# powermgr.net
KiCad netlist of a schematic drawn in EAGLE
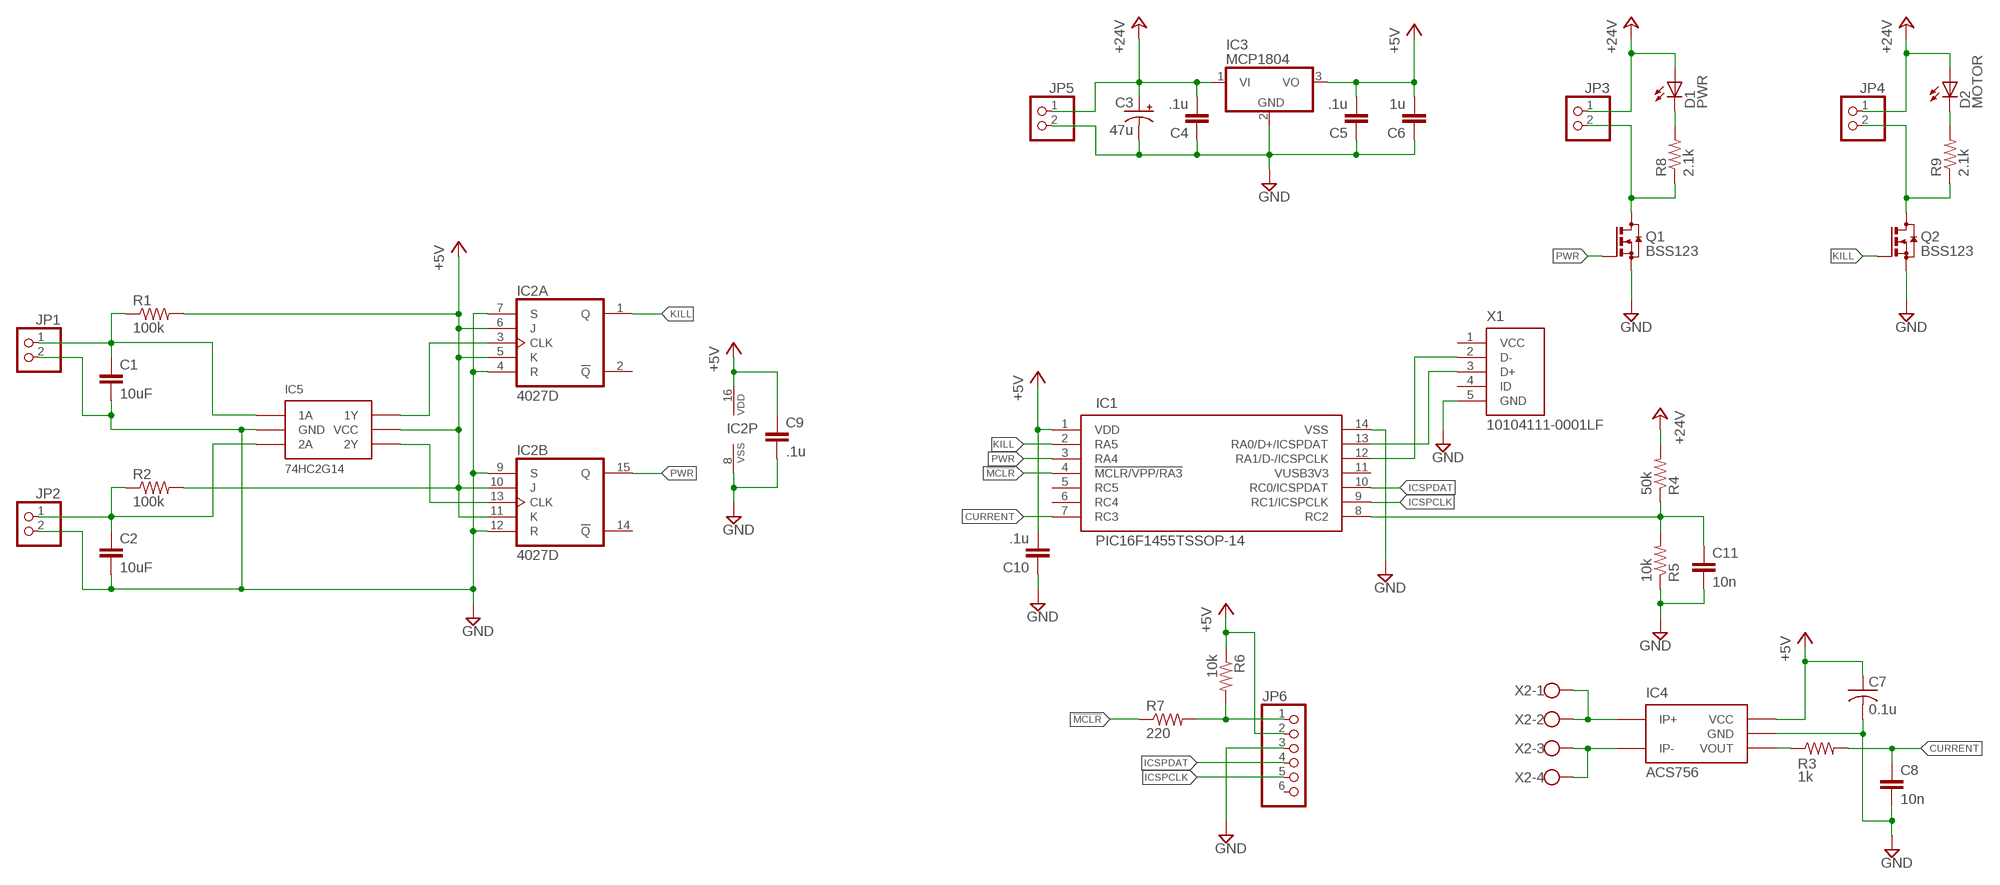
[diagram p0: schematic, sheet 1]

(export (version "E")
  (design (tool "Eeschema 10.0.6"))
  (components
    (comp (ref "C1")
      (value "10uF")
      (footprint "eagle-import:C0805")
      (libsource (lib "eagle-import") (part "C-EUC0805"))
    )
    (comp (ref "C2")
      (value "10uF")
      (footprint "eagle-import:C0805")
      (libsource (lib "eagle-import") (part "C-EUC0805"))
    )
    (comp (ref "C3")
      (value "47u")
      (footprint "eagle-import:E2,5-6")
      (libsource (lib "eagle-import") (part "CPOL-USE2.5-6"))
    )
    (comp (ref "C4")
      (value ".1u")
      (footprint "eagle-import:C0805")
      (libsource (lib "eagle-import") (part "C-EUC0805"))
    )
    (comp (ref "C5")
      (value ".1u")
      (footprint "eagle-import:C0805")
      (libsource (lib "eagle-import") (part "C-EUC0805"))
    )
    (comp (ref "C6")
      (value "1u")
      (footprint "eagle-import:C0805")
      (libsource (lib "eagle-import") (part "C-EUC0805"))
    )
    (comp (ref "C7")
      (value "0.1u")
      (footprint "eagle-import:C1206K")
      (libsource (lib "eagle-import") (part "C-USC1206K"))
    )
    (comp (ref "C8")
      (value "10n")
      (footprint "eagle-import:C0603K")
      (libsource (lib "eagle-import") (part "C-EUC0603K"))
    )
    (comp (ref "C9")
      (value ".1u")
      (footprint "eagle-import:C0603K")
      (libsource (lib "eagle-import") (part "C-EUC0603K"))
    )
    (comp (ref "C10")
      (value ".1u")
      (footprint "eagle-import:C0603K")
      (libsource (lib "eagle-import") (part "C-EUC0603K"))
    )
    (comp (ref "C11")
      (value "10n")
      (footprint "eagle-import:C0603K")
      (libsource (lib "eagle-import") (part "C-EUC0603K"))
    )
    (comp (ref "D1")
      (value "PWR")
      (footprint "eagle-import:CHIP-LED0805")
      (libsource (lib "eagle-import") (part "LEDCHIP-LED0805"))
    )
    (comp (ref "D2")
      (value "MOTOR")
      (footprint "eagle-import:CHIP-LED0805")
      (libsource (lib "eagle-import") (part "LEDCHIP-LED0805"))
    )
    (comp (ref "IC1")
      (value "PIC16F1455TSSOP-14")
      (footprint "eagle-import:TSSOP-14")
      (libsource (lib "eagle-import") (part "PIC16F1455TSSOP-14"))
    )
    (comp (ref "IC2")
      (value "4027D")
      (footprint "eagle-import:SO16")
      (libsource (lib "eagle-import") (part "4027D"))
    )
    (comp (ref "IC3")
      (value "MCP1804")
      (footprint "eagle-import:SOT223")
      (libsource (lib "eagle-import") (part "MCP1703DB"))
    )
    (comp (ref "IC4")
      (value "ACS756")
      (footprint "eagle-import:5PFF")
      (libsource (lib "eagle-import") (part "ACS756"))
    )
    (comp (ref "IC5")
      (value "74HC2G14")
      (footprint "eagle-import:TSSOP-6")
      (libsource (lib "eagle-import") (part "74HC2G14"))
    )
    (comp (ref "JP1")
      (value "PINHD-1X2")
      (footprint "eagle-import:1X02")
      (libsource (lib "eagle-import") (part "PINHD-1X2"))
    )
    (comp (ref "JP2")
      (value "PINHD-1X2")
      (footprint "eagle-import:1X02")
      (libsource (lib "eagle-import") (part "PINHD-1X2"))
    )
    (comp (ref "JP3")
      (value "PINHD-1X2")
      (footprint "eagle-import:1X02")
      (libsource (lib "eagle-import") (part "PINHD-1X2"))
    )
    (comp (ref "JP4")
      (value "PINHD-1X2")
      (footprint "eagle-import:1X02")
      (libsource (lib "eagle-import") (part "PINHD-1X2"))
    )
    (comp (ref "JP5")
      (value "PINHD-1X2")
      (footprint "eagle-import:1X02")
      (libsource (lib "eagle-import") (part "PINHD-1X2"))
    )
    (comp (ref "JP6")
      (value "PINHD-1X6")
      (footprint "eagle-import:1X06")
      (libsource (lib "eagle-import") (part "PINHD-1X6"))
    )
    (comp (ref "Q1")
      (value "BSS123")
      (footprint "eagle-import:SOT23")
      (libsource (lib "eagle-import") (part "BSS123"))
    )
    (comp (ref "Q2")
      (value "BSS123")
      (footprint "eagle-import:SOT23")
      (libsource (lib "eagle-import") (part "BSS123"))
    )
    (comp (ref "R1")
      (value "100k")
      (footprint "eagle-import:R0805")
      (libsource (lib "eagle-import") (part "R-US_R0805"))
    )
    (comp (ref "R2")
      (value "100k")
      (footprint "eagle-import:R0805")
      (libsource (lib "eagle-import") (part "R-US_R0805"))
    )
    (comp (ref "R3")
      (value "1k")
      (footprint "eagle-import:R0603")
      (libsource (lib "eagle-import") (part "R-US_R0603"))
    )
    (comp (ref "R4")
      (value "50k")
      (footprint "eagle-import:R0603")
      (libsource (lib "eagle-import") (part "R-US_R0603"))
    )
    (comp (ref "R5")
      (value "10k")
      (footprint "eagle-import:R0603")
      (libsource (lib "eagle-import") (part "R-US_R0603"))
    )
    (comp (ref "R6")
      (value "10k")
      (footprint "eagle-import:R0603")
      (libsource (lib "eagle-import") (part "R-US_R0603"))
    )
    (comp (ref "R7")
      (value "220")
      (footprint "eagle-import:R0603")
      (libsource (lib "eagle-import") (part "R-US_R0603"))
    )
    (comp (ref "R8")
      (value "2.1k")
      (footprint "eagle-import:R0805")
      (libsource (lib "eagle-import") (part "R-US_R0805"))
    )
    (comp (ref "R9")
      (value "2.1k")
      (footprint "eagle-import:R0805")
      (libsource (lib "eagle-import") (part "R-US_R0805"))
    )
    (comp (ref "X1")
      (value "10104111-0001LF")
      (footprint "eagle-import:USBAB")
      (libsource (lib "eagle-import") (part "10104111-0001LF"))
    )
    (comp (ref "X2")
      (value "W237-4")
      (footprint "eagle-import:W237-4")
      (libsource (lib "eagle-import") (part "W237-4"))
    )
  )
  (nets
    (net (code "1") (name "+5V") (class "Default")
      (node (ref "C10") (pin "2") (pinfunction "2_2") (pintype "passive"))
      (node (ref "C5") (pin "2") (pinfunction "2_2") (pintype "passive"))
      (node (ref "C6") (pin "2") (pinfunction "2_2") (pintype "passive"))
      (node (ref "C7") (pin "1") (pinfunction "1_1") (pintype "passive"))
      (node (ref "C9") (pin "1") (pinfunction "1_1") (pintype "passive"))
      (node (ref "IC1") (pin "1") (pinfunction "VDD_1") (pintype "power_in"))
      (node (ref "IC2") (pin "10") (pinfunction "J_10") (pintype "input"))
      (node (ref "IC2") (pin "11") (pinfunction "K_11") (pintype "input"))
      (node (ref "IC2") (pin "16") (pinfunction "VDD_16") (pintype "power_in"))
      (node (ref "IC2") (pin "5") (pinfunction "K_5") (pintype "input"))
      (node (ref "IC2") (pin "6") (pinfunction "J_6") (pintype "input"))
      (node (ref "IC3") (pin "3") (pinfunction "VO_3") (pintype "passive"))
      (node (ref "IC4") (pin "1") (pinfunction "VCC_1") (pintype "bidirectional"))
      (node (ref "IC5") (pin "5") (pinfunction "VCC_5") (pintype "bidirectional"))
      (node (ref "JP6") (pin "2") (pinfunction "2_2") (pintype "passive"))
      (node (ref "R1") (pin "2") (pinfunction "2_2") (pintype "passive"))
      (node (ref "R2") (pin "2") (pinfunction "2_2") (pintype "passive"))
      (node (ref "R6") (pin "1") (pinfunction "1_1") (pintype "passive"))
    )
    (net (code "2") (name "+24V") (class "Default")
      (node (ref "C3") (pin "+") (pinfunction "+_+") (pintype "passive"))
      (node (ref "C4") (pin "2") (pinfunction "2_2") (pintype "passive"))
      (node (ref "D1") (pin "A") (pinfunction "A_A") (pintype "passive"))
      (node (ref "D2") (pin "A") (pinfunction "A_A") (pintype "passive"))
      (node (ref "IC3") (pin "1") (pinfunction "VI_1") (pintype "input"))
      (node (ref "JP3") (pin "1") (pinfunction "1_1") (pintype "passive"))
      (node (ref "JP4") (pin "1") (pinfunction "1_1") (pintype "passive"))
      (node (ref "JP5") (pin "1") (pinfunction "1_1") (pintype "passive"))
      (node (ref "R4") (pin "2") (pinfunction "2_2") (pintype "passive"))
    )
    (net (code "3") (name "/~{MCLR}") (class "Default")
      (node (ref "IC1") (pin "4") (pinfunction "~{MCLR/VPP/RA3}_4") (pintype "bidirectional"))
      (node (ref "R7") (pin "1") (pinfunction "1_1") (pintype "passive"))
    )
    (net (code "4") (name "CURRENT") (class "Default")
      (node (ref "C8") (pin "1") (pinfunction "1_1") (pintype "passive"))
      (node (ref "IC1") (pin "7") (pinfunction "RC3_7") (pintype "bidirectional"))
      (node (ref "R3") (pin "2") (pinfunction "2_2") (pintype "passive"))
    )
    (net (code "5") (name "GND") (class "Default")
      (node (ref "C1") (pin "2") (pinfunction "2_2") (pintype "passive"))
      (node (ref "C10") (pin "1") (pinfunction "1_1") (pintype "passive"))
      (node (ref "C11") (pin "2") (pinfunction "2_2") (pintype "passive"))
      (node (ref "C2") (pin "2") (pinfunction "2_2") (pintype "passive"))
      (node (ref "C3") (pin "-") (pinfunction "-_-") (pintype "passive"))
      (node (ref "C4") (pin "1") (pinfunction "1_1") (pintype "passive"))
      (node (ref "C5") (pin "1") (pinfunction "1_1") (pintype "passive"))
      (node (ref "C6") (pin "1") (pinfunction "1_1") (pintype "passive"))
      (node (ref "C7") (pin "2") (pinfunction "2_2") (pintype "passive"))
      (node (ref "C8") (pin "2") (pinfunction "2_2") (pintype "passive"))
      (node (ref "C9") (pin "2") (pinfunction "2_2") (pintype "passive"))
      (node (ref "IC1") (pin "14") (pinfunction "VSS_14") (pintype "power_in"))
      (node (ref "IC2") (pin "12") (pinfunction "R_12") (pintype "input"))
      (node (ref "IC2") (pin "4") (pinfunction "R_4") (pintype "input"))
      (node (ref "IC2") (pin "7") (pinfunction "S_7") (pintype "input"))
      (node (ref "IC2") (pin "8") (pinfunction "VSS_8") (pintype "power_in"))
      (node (ref "IC2") (pin "9") (pinfunction "S_9") (pintype "input"))
      (node (ref "IC3") (pin "2") (pinfunction "GND_2") (pintype "passive"))
      (node (ref "IC4") (pin "2") (pinfunction "GND_2") (pintype "bidirectional"))
      (node (ref "IC5") (pin "2") (pinfunction "GND_2") (pintype "bidirectional"))
      (node (ref "JP1") (pin "2") (pinfunction "2_2") (pintype "passive"))
      (node (ref "JP2") (pin "2") (pinfunction "2_2") (pintype "passive"))
      (node (ref "JP5") (pin "2") (pinfunction "2_2") (pintype "passive"))
      (node (ref "JP6") (pin "3") (pinfunction "3_3") (pintype "passive"))
      (node (ref "Q1") (pin "2") (pinfunction "S_2") (pintype "passive"))
      (node (ref "Q2") (pin "2") (pinfunction "S_2") (pintype "passive"))
      (node (ref "R5") (pin "1") (pinfunction "1_1") (pintype "passive"))
      (node (ref "X1") (pin "5") (pinfunction "GND_5") (pintype "bidirectional"))
    )
    (net (code "6") (name "ICSPCLK") (class "Default")
      (node (ref "IC1") (pin "9") (pinfunction "RC1/ICSPCLK_9") (pintype "bidirectional"))
      (node (ref "JP6") (pin "5") (pinfunction "5_5") (pintype "passive"))
    )
    (net (code "7") (name "ICSPDAT") (class "Default")
      (node (ref "IC1") (pin "10") (pinfunction "RC0/ICSPDAT_10") (pintype "bidirectional"))
      (node (ref "JP6") (pin "4") (pinfunction "4_4") (pintype "passive"))
    )
    (net (code "8") (name "KILL") (class "Default")
      (node (ref "IC1") (pin "2") (pinfunction "RA5_2") (pintype "bidirectional"))
      (node (ref "IC2") (pin "1") (pinfunction "Q_1") (pintype "output"))
      (node (ref "Q2") (pin "1") (pinfunction "G_1") (pintype "passive"))
    )
    (net (code "9") (name "Net-(D1-PadC)") (class "Default")
      (node (ref "D1") (pin "C") (pinfunction "C_C") (pintype "passive"))
      (node (ref "R8") (pin "2") (pinfunction "2_2") (pintype "passive"))
    )
    (net (code "10") (name "Net-(D2-PadC)") (class "Default")
      (node (ref "D2") (pin "C") (pinfunction "C_C") (pintype "passive"))
      (node (ref "R9") (pin "2") (pinfunction "2_2") (pintype "passive"))
    )
    (net (code "11") (name "Net-(IC1-RA0{slash}D+{slash}ICSPDAT)") (class "Default")
      (node (ref "IC1") (pin "13") (pinfunction "RA0/D+/ICSPDAT_13") (pintype "bidirectional"))
      (node (ref "X1") (pin "3") (pinfunction "D+_3") (pintype "bidirectional"))
    )
    (net (code "12") (name "Net-(IC1-RA1{slash}D-{slash}ICSPCLK)") (class "Default")
      (node (ref "IC1") (pin "12") (pinfunction "RA1/D-/ICSPCLK_12") (pintype "bidirectional"))
      (node (ref "X1") (pin "2") (pinfunction "D-_2") (pintype "bidirectional"))
    )
    (net (code "13") (name "Net-(IC1-RC2)") (class "Default")
      (node (ref "C11") (pin "1") (pinfunction "1_1") (pintype "passive"))
      (node (ref "IC1") (pin "8") (pinfunction "RC2_8") (pintype "bidirectional"))
      (node (ref "R4") (pin "1") (pinfunction "1_1") (pintype "passive"))
      (node (ref "R5") (pin "2") (pinfunction "2_2") (pintype "passive"))
    )
    (net (code "14") (name "Net-(IC2A-CLK)") (class "Default")
      (node (ref "IC2") (pin "3") (pinfunction "CLK_3") (pintype "input"))
      (node (ref "IC5") (pin "6") (pinfunction "1Y_6") (pintype "bidirectional"))
    )
    (net (code "15") (name "Net-(IC2B-CLK)") (class "Default")
      (node (ref "IC2") (pin "13") (pinfunction "CLK_13") (pintype "input"))
      (node (ref "IC5") (pin "4") (pinfunction "2Y_4") (pintype "bidirectional"))
    )
    (net (code "16") (name "Net-(IC4-IP+)") (class "Default")
      (node (ref "IC4") (pin "4") (pinfunction "IP+_4") (pintype "bidirectional"))
      (node (ref "X2") (pin "1") (pinfunction "KL_1") (pintype "passive"))
      (node (ref "X2") (pin "2") (pinfunction "KL_2") (pintype "passive"))
    )
    (net (code "17") (name "Net-(IC4-IP-)") (class "Default")
      (node (ref "IC4") (pin "5") (pinfunction "IP-_5") (pintype "bidirectional"))
      (node (ref "X2") (pin "3") (pinfunction "KL_3") (pintype "passive"))
      (node (ref "X2") (pin "4") (pinfunction "KL_4") (pintype "passive"))
    )
    (net (code "18") (name "Net-(IC4-VOUT)") (class "Default")
      (node (ref "IC4") (pin "3") (pinfunction "VOUT_3") (pintype "bidirectional"))
      (node (ref "R3") (pin "1") (pinfunction "1_1") (pintype "passive"))
    )
    (net (code "19") (name "Net-(IC5-1A)") (class "Default")
      (node (ref "C1") (pin "1") (pinfunction "1_1") (pintype "passive"))
      (node (ref "IC5") (pin "1") (pinfunction "1A_1") (pintype "bidirectional"))
      (node (ref "JP1") (pin "1") (pinfunction "1_1") (pintype "passive"))
      (node (ref "R1") (pin "1") (pinfunction "1_1") (pintype "passive"))
    )
    (net (code "20") (name "Net-(IC5-2A)") (class "Default")
      (node (ref "C2") (pin "1") (pinfunction "1_1") (pintype "passive"))
      (node (ref "IC5") (pin "3") (pinfunction "2A_3") (pintype "bidirectional"))
      (node (ref "JP2") (pin "1") (pinfunction "1_1") (pintype "passive"))
      (node (ref "R2") (pin "1") (pinfunction "1_1") (pintype "passive"))
    )
    (net (code "21") (name "Net-(JP6-Pad1)") (class "Default")
      (node (ref "JP6") (pin "1") (pinfunction "1_1") (pintype "passive"))
      (node (ref "R6") (pin "2") (pinfunction "2_2") (pintype "passive"))
      (node (ref "R7") (pin "2") (pinfunction "2_2") (pintype "passive"))
    )
    (net (code "22") (name "Net-(Q1-D)") (class "Default")
      (node (ref "JP3") (pin "2") (pinfunction "2_2") (pintype "passive"))
      (node (ref "Q1") (pin "3") (pinfunction "D_3") (pintype "passive"))
      (node (ref "R8") (pin "1") (pinfunction "1_1") (pintype "passive"))
    )
    (net (code "23") (name "Net-(Q2-D)") (class "Default")
      (node (ref "JP4") (pin "2") (pinfunction "2_2") (pintype "passive"))
      (node (ref "Q2") (pin "3") (pinfunction "D_3") (pintype "passive"))
      (node (ref "R9") (pin "1") (pinfunction "1_1") (pintype "passive"))
    )
    (net (code "24") (name "PWR") (class "Default")
      (node (ref "IC1") (pin "3") (pinfunction "RA4_3") (pintype "bidirectional"))
      (node (ref "IC2") (pin "15") (pinfunction "Q_15") (pintype "output"))
      (node (ref "Q1") (pin "1") (pinfunction "G_1") (pintype "passive"))
    )
    (net (code "25") (name "unconnected-(IC1-RC4-Pad6)") (class "Default")
      (node (ref "IC1") (pin "6") (pinfunction "RC4_6") (pintype "bidirectional"))
    )
    (net (code "26") (name "unconnected-(IC1-RC5-Pad5)") (class "Default")
      (node (ref "IC1") (pin "5") (pinfunction "RC5_5") (pintype "bidirectional"))
    )
    (net (code "27") (name "unconnected-(IC1-VUSB3V3-Pad11)") (class "Default")
      (node (ref "IC1") (pin "11") (pinfunction "VUSB3V3_11") (pintype "bidirectional"))
    )
    (net (code "28") (name "unconnected-(IC2A-~{Q}-Pad2)") (class "Default")
      (node (ref "IC2") (pin "2") (pinfunction "~{Q}_2") (pintype "output"))
    )
    (net (code "29") (name "unconnected-(IC2B-~{Q}-Pad14)") (class "Default")
      (node (ref "IC2") (pin "14") (pinfunction "~{Q}_14") (pintype "output"))
    )
    (net (code "30") (name "unconnected-(JP6-Pad6)") (class "Default")
      (node (ref "JP6") (pin "6") (pinfunction "6_6") (pintype "passive"))
    )
    (net (code "31") (name "unconnected-(X1-ID-Pad4)") (class "Default")
      (node (ref "X1") (pin "4") (pinfunction "ID_4") (pintype "bidirectional"))
    )
    (net (code "32") (name "unconnected-(X1-VCC-Pad1)") (class "Default")
      (node (ref "X1") (pin "1") (pinfunction "VCC_1") (pintype "bidirectional"))
    )
  )
)
